# PROJETO_COMPLETO.net
KiCad netlist of a schematic drawn in EAGLE
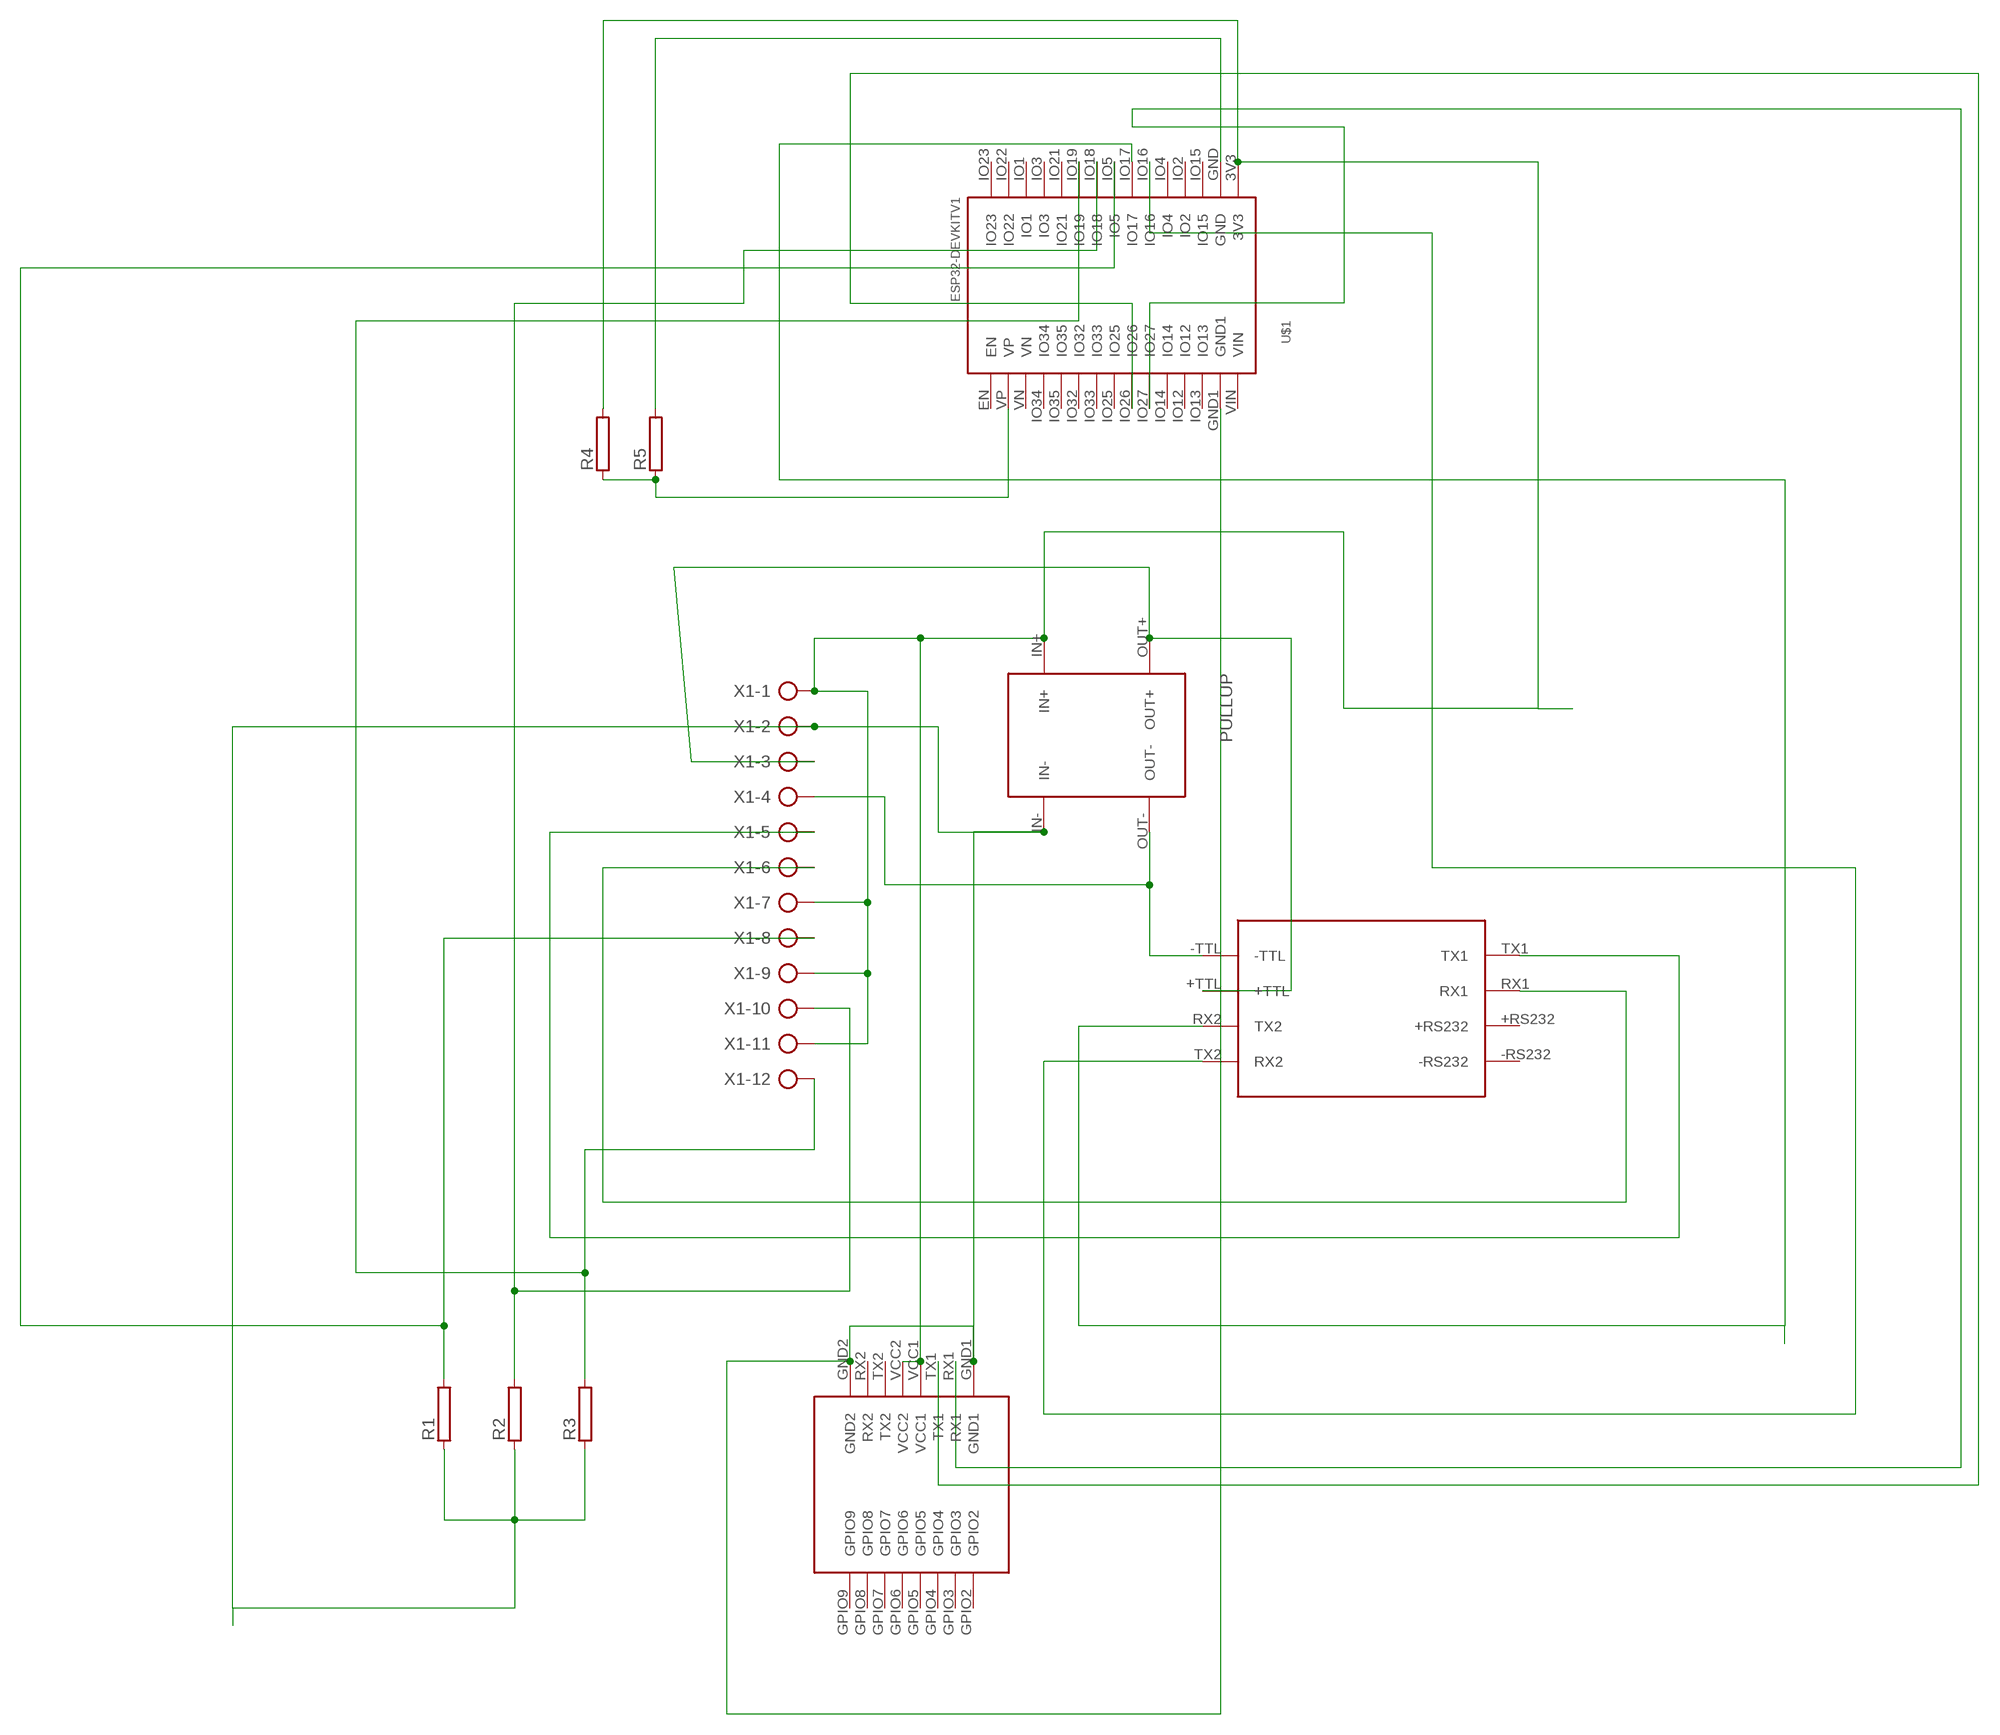
[diagram p0: schematic, sheet 1]

(export (version "E")
  (design (tool "Eeschema 10.0.6"))
  (components
    (comp (ref "R1")
      (value "RAC01")
      (footprint "eagle-import:AC01")
      (libsource (lib "eagle-import") (part "RAC01"))
    )
    (comp (ref "R2")
      (value "RAC01")
      (footprint "eagle-import:AC01")
      (libsource (lib "eagle-import") (part "RAC01"))
    )
    (comp (ref "R3")
      (value "RAC01")
      (footprint "eagle-import:AC01")
      (libsource (lib "eagle-import") (part "RAC01"))
    )
    (comp (ref "R4")
      (value "RAC01")
      (footprint "eagle-import:AC01")
      (libsource (lib "eagle-import") (part "RAC01"))
    )
    (comp (ref "R5")
      (value "RAC01")
      (footprint "eagle-import:AC01")
      (libsource (lib "eagle-import") (part "RAC01"))
    )
    (comp (ref "U$1")
      (value "ESP32DEVKITV1")
      (footprint "eagle-import:ESP32-DEVKITV1")
      (libsource (lib "eagle-import") (part "ESP32DEVKITV1"))
    )
    (comp (ref "U$2")
      (value "RADIOENGE")
      (footprint "eagle-import:RADIOENGE")
      (libsource (lib "eagle-import") (part "RADIOENGE"))
    )
    (comp (ref "U$3")
      (value "MAX3232")
      (footprint "eagle-import:MAX3232")
      (libsource (lib "eagle-import") (part "MAX3232"))
    )
    (comp (ref "U$4")
      (value "PULLUP")
      (footprint "eagle-import:PULLUP")
      (libsource (lib "eagle-import") (part "PULLUP"))
    )
    (comp (ref "X1")
      (value "AK500/12-H")
      (footprint "eagle-import:AK500_12-H")
      (libsource (lib "eagle-import") (part "AK500/12-H"))
    )
  )
  (nets
    (net (code "1") (name "Net-(R4-Pad1)") (class "Default")
      (node (ref "R4") (pin "1") (pinfunction "1_1") (pintype "passive"))
      (node (ref "R5") (pin "1") (pinfunction "1_1") (pintype "passive"))
      (node (ref "U$1") (pin "VP") (pinfunction "VP_VP") (pintype "bidirectional"))
    )
    (net (code "2") (name "Net-(R5-Pad2)") (class "Default")
      (node (ref "R5") (pin "2") (pinfunction "2_2") (pintype "passive"))
      (node (ref "U$1") (pin "GND") (pinfunction "GND_GND") (pintype "bidirectional"))
    )
    (net (code "3") (name "Net-(U$1-PadIO26)") (class "Default")
      (node (ref "U$1") (pin "IO26") (pinfunction "IO26_IO26") (pintype "bidirectional"))
      (node (ref "U$2") (pin "TX1") (pinfunction "TX1_TX1") (pintype "bidirectional"))
    )
    (net (code "4") (name "Net-(U$1-PadIO27)") (class "Default")
      (node (ref "U$1") (pin "IO27") (pinfunction "IO27_IO27") (pintype "bidirectional"))
      (node (ref "U$2") (pin "RX1") (pinfunction "RX1_RX1") (pintype "bidirectional"))
    )
    (net (code "5") (name "Net-(U$3-RX2)") (class "Default")
      (node (ref "U$1") (pin "IO16") (pinfunction "IO16_IO16") (pintype "bidirectional"))
      (node (ref "U$3") (pin "TX2") (pinfunction "RX2_TX2") (pintype "bidirectional"))
    )
    (net (code "6") (name "Net-(U$3-TX2)") (class "Default")
      (node (ref "U$1") (pin "IO17") (pinfunction "IO17_IO17") (pintype "bidirectional"))
      (node (ref "U$3") (pin "RX2") (pinfunction "TX2_RX2") (pintype "bidirectional"))
    )
    (net (code "7") (name "Net-(X1A-KL)") (class "Default")
      (node (ref "R4") (pin "2") (pinfunction "2_2") (pintype "passive"))
      (node (ref "U$1") (pin "3V3") (pinfunction "3V3_3V3") (pintype "bidirectional"))
      (node (ref "U$2") (pin "VCC1") (pinfunction "VCC1_VCC1") (pintype "bidirectional"))
      (node (ref "U$2") (pin "VCC2") (pinfunction "VCC2_VCC2") (pintype "bidirectional"))
      (node (ref "U$4") (pin "IN+") (pinfunction "IN+_IN+") (pintype "bidirectional"))
      (node (ref "X1") (pin "1") (pinfunction "KL_1") (pintype "passive"))
      (node (ref "X1") (pin "11") (pinfunction "KL_11") (pintype "passive"))
      (node (ref "X1") (pin "7") (pinfunction "KL_7") (pintype "passive"))
      (node (ref "X1") (pin "9") (pinfunction "KL_9") (pintype "passive"))
    )
    (net (code "8") (name "Net-(X1B-KL)") (class "Default")
      (node (ref "R2") (pin "2") (pinfunction "2_2") (pintype "passive"))
      (node (ref "U$1") (pin "IO18") (pinfunction "IO18_IO18") (pintype "bidirectional"))
      (node (ref "X1") (pin "10") (pinfunction "KL_10") (pintype "passive"))
    )
    (net (code "9") (name "Net-(X1D-KL)") (class "Default")
      (node (ref "R3") (pin "2") (pinfunction "2_2") (pintype "passive"))
      (node (ref "U$1") (pin "IO19") (pinfunction "IO19_IO19") (pintype "bidirectional"))
      (node (ref "X1") (pin "12") (pinfunction "KL_12") (pintype "passive"))
    )
    (net (code "10") (name "Net-(X1E-KL)") (class "Default")
      (node (ref "R1") (pin "1") (pinfunction "1_1") (pintype "passive"))
      (node (ref "R2") (pin "1") (pinfunction "1_1") (pintype "passive"))
      (node (ref "R3") (pin "1") (pinfunction "1_1") (pintype "passive"))
      (node (ref "U$1") (pin "GND1") (pinfunction "GND1_GND1") (pintype "bidirectional"))
      (node (ref "U$2") (pin "GND1") (pinfunction "GND1_GND1") (pintype "bidirectional"))
      (node (ref "U$2") (pin "GND2") (pinfunction "GND2_GND2") (pintype "bidirectional"))
      (node (ref "U$4") (pin "IN-") (pinfunction "IN-_IN-") (pintype "bidirectional"))
      (node (ref "X1") (pin "2") (pinfunction "KL_2") (pintype "passive"))
    )
    (net (code "11") (name "Net-(X1F-KL)") (class "Default")
      (node (ref "U$3") (pin "+TTL") (pinfunction "+TTL_+TTL") (pintype "bidirectional"))
      (node (ref "U$4") (pin "OUT+") (pinfunction "OUT+_OUT+") (pintype "bidirectional"))
      (node (ref "X1") (pin "3") (pinfunction "KL_3") (pintype "passive"))
    )
    (net (code "12") (name "Net-(X1G-KL)") (class "Default")
      (node (ref "U$3") (pin "-TTL") (pinfunction "-TTL_-TTL") (pintype "bidirectional"))
      (node (ref "U$4") (pin "OUT-") (pinfunction "OUT-_OUT-") (pintype "bidirectional"))
      (node (ref "X1") (pin "4") (pinfunction "KL_4") (pintype "passive"))
    )
    (net (code "13") (name "Net-(X1H-KL)") (class "Default")
      (node (ref "U$3") (pin "TX1") (pinfunction "TX1_TX1") (pintype "bidirectional"))
      (node (ref "X1") (pin "5") (pinfunction "KL_5") (pintype "passive"))
    )
    (net (code "14") (name "Net-(X1I-KL)") (class "Default")
      (node (ref "U$3") (pin "RX1") (pinfunction "RX1_RX1") (pintype "bidirectional"))
      (node (ref "X1") (pin "6") (pinfunction "KL_6") (pintype "passive"))
    )
    (net (code "15") (name "Net-(X1K-KL)") (class "Default")
      (node (ref "R1") (pin "2") (pinfunction "2_2") (pintype "passive"))
      (node (ref "U$1") (pin "IO5") (pinfunction "IO5_IO5") (pintype "bidirectional"))
      (node (ref "X1") (pin "8") (pinfunction "KL_8") (pintype "passive"))
    )
    (net (code "16") (name "unconnected-(U$1-PadEN)") (class "Default")
      (node (ref "U$1") (pin "EN") (pinfunction "EN_EN") (pintype "bidirectional"))
    )
    (net (code "17") (name "unconnected-(U$1-PadIO1)") (class "Default")
      (node (ref "U$1") (pin "IO1") (pinfunction "IO1_IO1") (pintype "bidirectional"))
    )
    (net (code "18") (name "unconnected-(U$1-PadIO2)") (class "Default")
      (node (ref "U$1") (pin "IO2") (pinfunction "IO2_IO2") (pintype "bidirectional"))
    )
    (net (code "19") (name "unconnected-(U$1-PadIO3)") (class "Default")
      (node (ref "U$1") (pin "IO3") (pinfunction "IO3_IO3") (pintype "bidirectional"))
    )
    (net (code "20") (name "unconnected-(U$1-PadIO4)") (class "Default")
      (node (ref "U$1") (pin "IO4") (pinfunction "IO4_IO4") (pintype "bidirectional"))
    )
    (net (code "21") (name "unconnected-(U$1-PadIO12)") (class "Default")
      (node (ref "U$1") (pin "IO12") (pinfunction "IO12_IO12") (pintype "bidirectional"))
    )
    (net (code "22") (name "unconnected-(U$1-PadIO13)") (class "Default")
      (node (ref "U$1") (pin "IO13") (pinfunction "IO13_IO13") (pintype "bidirectional"))
    )
    (net (code "23") (name "unconnected-(U$1-PadIO14)") (class "Default")
      (node (ref "U$1") (pin "IO14") (pinfunction "IO14_IO14") (pintype "bidirectional"))
    )
    (net (code "24") (name "unconnected-(U$1-PadIO15)") (class "Default")
      (node (ref "U$1") (pin "IO15") (pinfunction "IO15_IO15") (pintype "bidirectional"))
    )
    (net (code "25") (name "unconnected-(U$1-PadIO21)") (class "Default")
      (node (ref "U$1") (pin "IO21") (pinfunction "IO21_IO21") (pintype "bidirectional"))
    )
    (net (code "26") (name "unconnected-(U$1-PadIO22)") (class "Default")
      (node (ref "U$1") (pin "IO22") (pinfunction "IO22_IO22") (pintype "bidirectional"))
    )
    (net (code "27") (name "unconnected-(U$1-PadIO23)") (class "Default")
      (node (ref "U$1") (pin "IO23") (pinfunction "IO23_IO23") (pintype "bidirectional"))
    )
    (net (code "28") (name "unconnected-(U$1-PadIO25)") (class "Default")
      (node (ref "U$1") (pin "IO25") (pinfunction "IO25_IO25") (pintype "bidirectional"))
    )
    (net (code "29") (name "unconnected-(U$1-PadIO32)") (class "Default")
      (node (ref "U$1") (pin "IO32") (pinfunction "IO32_IO32") (pintype "bidirectional"))
    )
    (net (code "30") (name "unconnected-(U$1-PadIO33)") (class "Default")
      (node (ref "U$1") (pin "IO33") (pinfunction "IO33_IO33") (pintype "bidirectional"))
    )
    (net (code "31") (name "unconnected-(U$1-PadIO34)") (class "Default")
      (node (ref "U$1") (pin "IO34") (pinfunction "IO34_IO34") (pintype "bidirectional"))
    )
    (net (code "32") (name "unconnected-(U$1-PadIO35)") (class "Default")
      (node (ref "U$1") (pin "IO35") (pinfunction "IO35_IO35") (pintype "bidirectional"))
    )
    (net (code "33") (name "unconnected-(U$1-PadVIN)") (class "Default")
      (node (ref "U$1") (pin "VIN") (pinfunction "VIN_VIN") (pintype "bidirectional"))
    )
    (net (code "34") (name "unconnected-(U$1-PadVN)") (class "Default")
      (node (ref "U$1") (pin "VN") (pinfunction "VN_VN") (pintype "bidirectional"))
    )
    (net (code "35") (name "unconnected-(U$2-PadGPIO2)") (class "Default")
      (node (ref "U$2") (pin "GPIO2") (pinfunction "GPIO2_GPIO2") (pintype "bidirectional"))
    )
    (net (code "36") (name "unconnected-(U$2-PadGPIO3)") (class "Default")
      (node (ref "U$2") (pin "GPIO3") (pinfunction "GPIO3_GPIO3") (pintype "bidirectional"))
    )
    (net (code "37") (name "unconnected-(U$2-PadGPIO4)") (class "Default")
      (node (ref "U$2") (pin "GPIO4") (pinfunction "GPIO4_GPIO4") (pintype "bidirectional"))
    )
    (net (code "38") (name "unconnected-(U$2-PadGPIO5)") (class "Default")
      (node (ref "U$2") (pin "GPIO5") (pinfunction "GPIO5_GPIO5") (pintype "bidirectional"))
    )
    (net (code "39") (name "unconnected-(U$2-PadGPIO6)") (class "Default")
      (node (ref "U$2") (pin "GPIO6") (pinfunction "GPIO6_GPIO6") (pintype "bidirectional"))
    )
    (net (code "40") (name "unconnected-(U$2-PadGPIO7)") (class "Default")
      (node (ref "U$2") (pin "GPIO7") (pinfunction "GPIO7_GPIO7") (pintype "bidirectional"))
    )
    (net (code "41") (name "unconnected-(U$2-PadGPIO8)") (class "Default")
      (node (ref "U$2") (pin "GPIO8") (pinfunction "GPIO8_GPIO8") (pintype "bidirectional"))
    )
    (net (code "42") (name "unconnected-(U$2-PadGPIO9)") (class "Default")
      (node (ref "U$2") (pin "GPIO9") (pinfunction "GPIO9_GPIO9") (pintype "bidirectional"))
    )
    (net (code "43") (name "unconnected-(U$2-PadRX2)") (class "Default")
      (node (ref "U$2") (pin "RX2") (pinfunction "RX2_RX2") (pintype "bidirectional"))
    )
    (net (code "44") (name "unconnected-(U$2-PadTX2)") (class "Default")
      (node (ref "U$2") (pin "TX2") (pinfunction "TX2_TX2") (pintype "bidirectional"))
    )
    (net (code "45") (name "unconnected-(U$3-Pad+RS232)") (class "Default")
      (node (ref "U$3") (pin "+RS232") (pinfunction "+RS232_+RS232") (pintype "bidirectional"))
    )
    (net (code "46") (name "unconnected-(U$3-Pad-RS232)") (class "Default")
      (node (ref "U$3") (pin "-RS232") (pinfunction "-RS232_-RS232") (pintype "bidirectional"))
    )
  )
)
